# Sheet1.net
KiCad netlist of a schematic drawn in Altium Designer
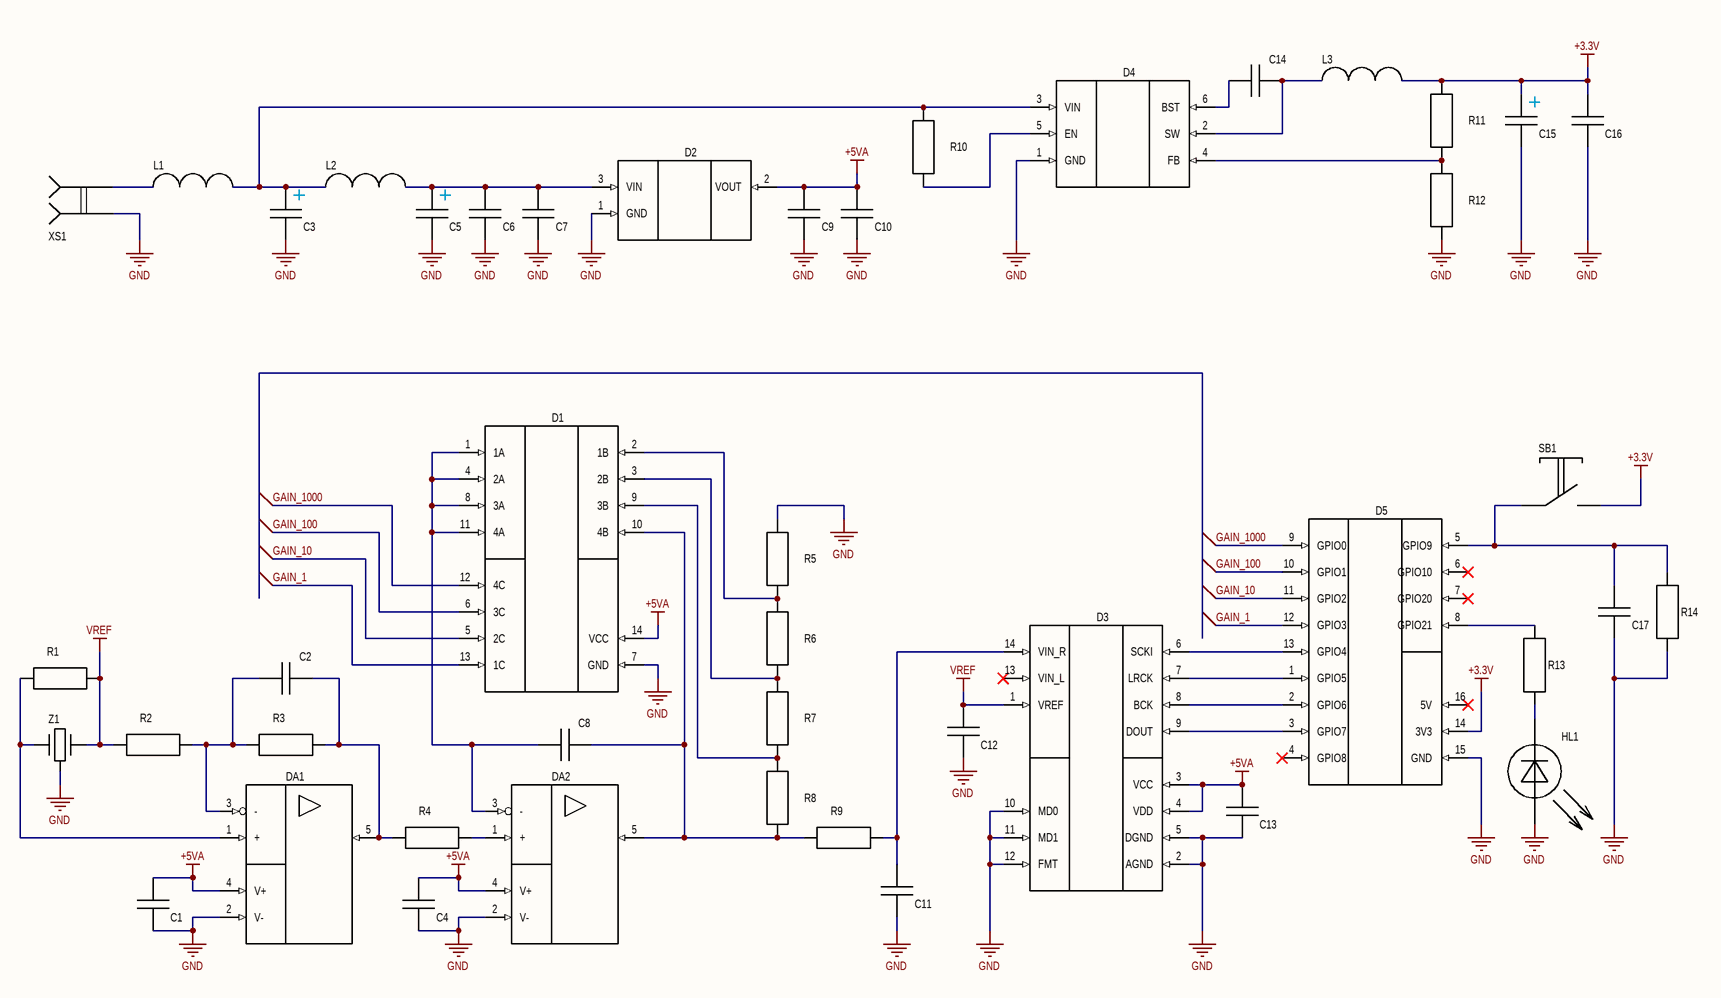
[diagram p0: Sheet1.SchDoc]

(export (version "E")
  (design (tool "Eeschema 10.0.6"))
  (components
    (comp (ref "C1")
      (value "100")
      (footprint "C_0603_(1608)")
      (description "Non-polarised capacitor")
      (fields (field (name "PART NUMBER") "GRM188R71H104KA93#") (field (name "MANUFACTURER") "MURATA"))
      (libsource (lib "GOSTBOM") (part "CAP_NONPOL"))
    )
    (comp (ref "C2")
      (value "100")
      (footprint "C_0603_(1608)")
      (description "Non-polarised capacitor")
      (fields (field (name "PART NUMBER") "GRM188R71H104KA93#") (field (name "MANUFACTURER") "MURATA"))
      (libsource (lib "GOSTBOM") (part "CAP_NONPOL"))
    )
    (comp (ref "C3")
      (value "100")
      (footprint "CP_D10_P5_L16")
      (description "Non-polarised capacitor")
      (fields (field (name "PART NUMBER") "GRM188R71H104KA93#") (field (name "MANUFACTURER") "MURATA"))
      (libsource (lib "GOSTBOM") (part "CAP_NONPOL"))
    )
    (comp (ref "C4")
      (value "100")
      (footprint "C_0603_(1608)")
      (description "Non-polarised capacitor")
      (fields (field (name "PART NUMBER") "GRM188R71H104KA93#") (field (name "MANUFACTURER") "MURATA"))
      (libsource (lib "GOSTBOM") (part "CAP_NONPOL"))
    )
    (comp (ref "C5")
      (value "100")
      (footprint "CP_D10_P5_L16")
      (description "Non-polarised capacitor")
      (fields (field (name "PART NUMBER") "GRM188R71H104KA93#") (field (name "MANUFACTURER") "MURATA"))
      (libsource (lib "GOSTBOM") (part "CAP_NONPOL"))
    )
    (comp (ref "C6")
      (value "100")
      (footprint "C_0603_(1608)")
      (description "Non-polarised capacitor")
      (fields (field (name "PART NUMBER") "GRM188R71H104KA93#") (field (name "MANUFACTURER") "MURATA"))
      (libsource (lib "GOSTBOM") (part "CAP_NONPOL"))
    )
    (comp (ref "C7")
      (value "100")
      (footprint "C_0603_(1608)")
      (description "Non-polarised capacitor")
      (fields (field (name "PART NUMBER") "GRM188R71H104KA93#") (field (name "MANUFACTURER") "MURATA"))
      (libsource (lib "GOSTBOM") (part "CAP_NONPOL"))
    )
    (comp (ref "C8")
      (value "100")
      (footprint "CAPC1608X90N")
      (description "Non-polarised capacitor")
      (fields (field (name "PART NUMBER") "GRM188R71H104KA93#") (field (name "MANUFACTURER") "MURATA"))
      (libsource (lib "GOSTBOM") (part "CAP_NONPOL"))
    )
    (comp (ref "C9")
      (value "100")
      (footprint "C_0603_(1608)")
      (description "Non-polarised capacitor")
      (fields (field (name "PART NUMBER") "GRM188R71H104KA93#") (field (name "MANUFACTURER") "MURATA"))
      (libsource (lib "GOSTBOM") (part "CAP_NONPOL"))
    )
    (comp (ref "C10")
      (value "100")
      (footprint "C_0603_(1608)")
      (description "Non-polarised capacitor")
      (fields (field (name "PART NUMBER") "GRM188R71H104KA93#") (field (name "MANUFACTURER") "MURATA"))
      (libsource (lib "GOSTBOM") (part "CAP_NONPOL"))
    )
    (comp (ref "C11")
      (value "100")
      (footprint "C_0603_(1608)")
      (description "Non-polarised capacitor")
      (fields (field (name "PART NUMBER") "GRM188R71H104KA93#") (field (name "MANUFACTURER") "MURATA"))
      (libsource (lib "GOSTBOM") (part "CAP_NONPOL"))
    )
    (comp (ref "C12")
      (value "100")
      (footprint "C_0603_(1608)")
      (description "Non-polarised capacitor")
      (fields (field (name "PART NUMBER") "GRM188R71H104KA93#") (field (name "MANUFACTURER") "MURATA"))
      (libsource (lib "GOSTBOM") (part "CAP_NONPOL"))
    )
    (comp (ref "C13")
      (value "100")
      (footprint "C_0603_(1608)")
      (description "Non-polarised capacitor")
      (fields (field (name "PART NUMBER") "GRM188R71H104KA93#") (field (name "MANUFACTURER") "MURATA"))
      (libsource (lib "GOSTBOM") (part "CAP_NONPOL"))
    )
    (comp (ref "C14")
      (value "100")
      (footprint "C_0603_(1608)")
      (description "Non-polarised capacitor")
      (fields (field (name "PART NUMBER") "GRM188R71H104KA93#") (field (name "MANUFACTURER") "MURATA"))
      (libsource (lib "GOSTBOM") (part "CAP_NONPOL"))
    )
    (comp (ref "C15")
      (value "100")
      (footprint "CP_D10_P5_L16")
      (description "Non-polarised capacitor")
      (fields (field (name "PART NUMBER") "GRM188R71H104KA93#") (field (name "MANUFACTURER") "MURATA"))
      (libsource (lib "GOSTBOM") (part "CAP_NONPOL"))
    )
    (comp (ref "C16")
      (value "100")
      (footprint "C_0603_(1608)")
      (description "Non-polarised capacitor")
      (fields (field (name "PART NUMBER") "GRM188R71H104KA93#") (field (name "MANUFACTURER") "MURATA"))
      (libsource (lib "GOSTBOM") (part "CAP_NONPOL"))
    )
    (comp (ref "C17")
      (value "100")
      (footprint "C_0603_(1608)")
      (description "Non-polarised capacitor")
      (fields (field (name "PART NUMBER") "GRM188R71H104KA93#") (field (name "MANUFACTURER") "MURATA"))
      (libsource (lib "GOSTBOM") (part "CAP_NONPOL"))
    )
    (comp (ref "D1")
      (value "Обозначение при заказе")
      (footprint "TSSOP14")
      (description "Описание свойств компонента")
      (libsource (lib "Schlib1") (part "SN74HC4066"))
    )
    (comp (ref "D2")
      (value "Обозначение при заказе")
      (footprint "SOT223")
      (description "Описание свойств компонента")
      (libsource (lib "Schlib1") (part "LD1117S50TR"))
    )
    (comp (ref "D3")
      (value "Обозначение при заказе")
      (footprint "SO-14")
      (description "Описание свойств компонента")
      (libsource (lib "Schlib1") (part "PCM1808"))
    )
    (comp (ref "D4")
      (value "Обозначение при заказе")
      (footprint "SOT23-6")
      (description "Описание свойств компонента")
      (libsource (lib "Schlib1") (part "MT1470"))
    )
    (comp (ref "D5")
      (value "Обозначение при заказе")
      (description "Описание свойств компонента")
      (libsource (lib "Schlib1") (part "ESP32C3"))
    )
    (comp (ref "DA1")
      (value "Обозначение при заказе")
      (footprint "TSOT23-5L")
      (description "Описание свойств компонента")
      (libsource (lib "Schlib1") (part "TLV6741"))
    )
    (comp (ref "DA2")
      (value "Обозначение при заказе")
      (footprint "TSOT23-5L")
      (description "Описание свойств компонента")
      (libsource (lib "Schlib1") (part "TLV6741"))
    )
    (comp (ref "HL1") (value "~") (footprint "ledrad3mm") (libsource (lib "sch") (part "LED")))
    (comp (ref "L1") (value "~") (footprint "C_0603_(1608)") (libsource (lib "sch") (part "Inductor")))
    (comp (ref "L2") (value "~") (footprint "C_0603_(1608)") (libsource (lib "sch") (part "Inductor")))
    (comp (ref "L3") (value "~") (footprint "SS0704") (libsource (lib "sch") (part "Inductor")))
    (comp (ref "R1")
      (value "CR 0402 4,7 кОм ±1%")
      (footprint "R_0603_(1608)")
      (fields (field (name "PART NUMBER") "CR0402-FX-4701G") (field (name "MANUFACTURER") "Bourns"))
      (libsource (lib "") (part "RESISTOR_1"))
    )
    (comp (ref "R2")
      (value "CR 0402 4,7 кОм ±1%")
      (footprint "R_0603_(1608)")
      (fields (field (name "PART NUMBER") "CR0402-FX-4701G") (field (name "MANUFACTURER") "Bourns"))
      (libsource (lib "") (part "RESISTOR_1"))
    )
    (comp (ref "R3")
      (value "CR 0402 4,7 кОм ±1%")
      (footprint "R_0603_(1608)")
      (fields (field (name "PART NUMBER") "CR0402-FX-4701G") (field (name "MANUFACTURER") "Bourns"))
      (libsource (lib "") (part "RESISTOR_1"))
    )
    (comp (ref "R4")
      (value "CR 0402 4,7 кОм ±1%")
      (footprint "R_0603_(1608)")
      (fields (field (name "PART NUMBER") "CR0402-FX-4701G") (field (name "MANUFACTURER") "Bourns"))
      (libsource (lib "") (part "RESISTOR_1"))
    )
    (comp (ref "R5")
      (value "CR 0402 4,7 кОм ±1%")
      (footprint "R_0603_(1608)")
      (fields (field (name "PART NUMBER") "CR0402-FX-4701G") (field (name "MANUFACTURER") "Bourns"))
      (libsource (lib "GOSTBOM") (part "RESISTOR"))
    )
    (comp (ref "R6")
      (value "CR 0402 4,7 кОм ±1%")
      (footprint "R_0603_(1608)")
      (fields (field (name "PART NUMBER") "CR0402-FX-4701G") (field (name "MANUFACTURER") "Bourns"))
      (libsource (lib "GOSTBOM") (part "RESISTOR"))
    )
    (comp (ref "R7")
      (value "CR 0402 4,7 кОм ±1%")
      (footprint "R_0603_(1608)")
      (fields (field (name "PART NUMBER") "CR0402-FX-4701G") (field (name "MANUFACTURER") "Bourns"))
      (libsource (lib "GOSTBOM") (part "RESISTOR"))
    )
    (comp (ref "R8")
      (value "CR 0402 4,7 кОм ±1%")
      (footprint "R_0603_(1608)")
      (fields (field (name "PART NUMBER") "CR0402-FX-4701G") (field (name "MANUFACTURER") "Bourns"))
      (libsource (lib "GOSTBOM") (part "RESISTOR"))
    )
    (comp (ref "R9")
      (value "CR 0402 4,7 кОм ±1%")
      (footprint "R_0603_(1608)")
      (fields (field (name "PART NUMBER") "CR0402-FX-4701G") (field (name "MANUFACTURER") "Bourns"))
      (libsource (lib "") (part "RESISTOR_1"))
    )
    (comp (ref "R10")
      (value "CR 0402 4,7 кОм ±1%")
      (footprint "R_0603_(1608)")
      (fields (field (name "PART NUMBER") "CR0402-FX-4701G") (field (name "MANUFACTURER") "Bourns"))
      (libsource (lib "GOSTBOM") (part "RESISTOR"))
    )
    (comp (ref "R11")
      (value "CR 0402 4,7 кОм ±1%")
      (footprint "R_0603_(1608)")
      (fields (field (name "PART NUMBER") "CR0402-FX-4701G") (field (name "MANUFACTURER") "Bourns"))
      (libsource (lib "GOSTBOM") (part "RESISTOR"))
    )
    (comp (ref "R12")
      (value "CR 0402 4,7 кОм ±1%")
      (footprint "R_0603_(1608)")
      (fields (field (name "PART NUMBER") "CR0402-FX-4701G") (field (name "MANUFACTURER") "Bourns"))
      (libsource (lib "GOSTBOM") (part "RESISTOR"))
    )
    (comp (ref "R13")
      (value "CR 0402 4,7 кОм ±1%")
      (footprint "R_0603_(1608)")
      (fields (field (name "PART NUMBER") "CR0402-FX-4701G") (field (name "MANUFACTURER") "Bourns"))
      (libsource (lib "GOSTBOM") (part "RESISTOR"))
    )
    (comp (ref "R14")
      (value "CR 0402 4,7 кОм ±1%")
      (footprint "R_0603_(1608)")
      (fields (field (name "PART NUMBER") "CR0402-FX-4701G") (field (name "MANUFACTURER") "Bourns"))
      (libsource (lib "GOSTBOM") (part "RESISTOR"))
    )
    (comp (ref "SB1") (value "~") (libsource (lib "sch") (part "SW-PB")))
    (comp (ref "XS1")
      (value "HYR-0142AR")
      (footprint "KLD-0202")
      (description "HYR-0142AR (GB-142AR) (BNC-7044), Разъем BNC, гнездо угловое, на плату")
      (libsource (lib "Connectors_templates") (part "XS2"))
    )
    (comp (ref "Z1") (value "~") (libsource (lib "sch") (part "XTALE")))
  )
  (nets
    (net (code "1") (name "+3.3V") (class "Default")
      (node (ref "C15") (pin "2") (pinfunction "2_2") (pintype "passive"))
      (node (ref "C16") (pin "2") (pinfunction "2_2") (pintype "passive"))
      (node (ref "D5") (pin "14") (pinfunction "3V3_14") (pintype "input"))
      (node (ref "L3") (pin "2") (pinfunction "2_2") (pintype "passive"))
      (node (ref "R11") (pin "2") (pinfunction "2_2") (pintype "passive"))
      (node (ref "SB1") (pin "2") (pinfunction "2_2") (pintype "passive"))
    )
    (net (code "2") (name "+5VA") (class "Default")
      (node (ref "C1") (pin "2") (pinfunction "2_2") (pintype "passive"))
      (node (ref "C10") (pin "2") (pinfunction "2_2") (pintype "passive"))
      (node (ref "C13") (pin "2") (pinfunction "2_2") (pintype "passive"))
      (node (ref "C4") (pin "2") (pinfunction "2_2") (pintype "passive"))
      (node (ref "C9") (pin "2") (pinfunction "2_2") (pintype "passive"))
      (node (ref "D1") (pin "14") (pinfunction "VCC_14") (pintype "input"))
      (node (ref "D2") (pin "2") (pinfunction "VOUT_2") (pintype "input"))
      (node (ref "D3") (pin "3") (pinfunction "VCC_3") (pintype "input"))
      (node (ref "D3") (pin "4") (pinfunction "VDD_4") (pintype "input"))
      (node (ref "DA1") (pin "4") (pinfunction "V+_4") (pintype "input"))
      (node (ref "DA2") (pin "4") (pinfunction "V+_4") (pintype "input"))
    )
    (net (code "3") (name "/GAIN_1") (class "Default")
      (node (ref "D1") (pin "13") (pinfunction "1C_13") (pintype "input"))
      (node (ref "D5") (pin "12") (pinfunction "GPIO3_12") (pintype "input"))
    )
    (net (code "4") (name "/GAIN_10") (class "Default")
      (node (ref "D1") (pin "5") (pinfunction "2C_5") (pintype "input"))
      (node (ref "D5") (pin "11") (pinfunction "GPIO2_11") (pintype "input"))
    )
    (net (code "5") (name "/GAIN_100") (class "Default")
      (node (ref "D1") (pin "6") (pinfunction "3C_6") (pintype "input"))
      (node (ref "D5") (pin "10") (pinfunction "GPIO1_10") (pintype "input"))
    )
    (net (code "6") (name "/GAIN_1000") (class "Default")
      (node (ref "D1") (pin "12") (pinfunction "4C_12") (pintype "input"))
      (node (ref "D5") (pin "9") (pinfunction "GPIO0_9") (pintype "input"))
    )
    (net (code "7") (name "GND") (class "Default")
      (node (ref "C1") (pin "1") (pinfunction "1_1") (pintype "passive"))
      (node (ref "C10") (pin "1") (pinfunction "1_1") (pintype "passive"))
      (node (ref "C11") (pin "1") (pinfunction "1_1") (pintype "passive"))
      (node (ref "C12") (pin "1") (pinfunction "1_1") (pintype "passive"))
      (node (ref "C13") (pin "1") (pinfunction "1_1") (pintype "passive"))
      (node (ref "C15") (pin "1") (pinfunction "1_1") (pintype "passive"))
      (node (ref "C16") (pin "1") (pinfunction "1_1") (pintype "passive"))
      (node (ref "C17") (pin "1") (pinfunction "1_1") (pintype "passive"))
      (node (ref "C3") (pin "1") (pinfunction "1_1") (pintype "passive"))
      (node (ref "C4") (pin "1") (pinfunction "1_1") (pintype "passive"))
      (node (ref "C5") (pin "1") (pinfunction "1_1") (pintype "passive"))
      (node (ref "C6") (pin "1") (pinfunction "1_1") (pintype "passive"))
      (node (ref "C7") (pin "1") (pinfunction "1_1") (pintype "passive"))
      (node (ref "C9") (pin "1") (pinfunction "1_1") (pintype "passive"))
      (node (ref "D1") (pin "7") (pinfunction "GND_7") (pintype "input"))
      (node (ref "D2") (pin "1") (pinfunction "GND_1") (pintype "input"))
      (node (ref "D3") (pin "10") (pinfunction "MD0_10") (pintype "input"))
      (node (ref "D3") (pin "11") (pinfunction "MD1_11") (pintype "input"))
      (node (ref "D3") (pin "12") (pinfunction "FMT_12") (pintype "input"))
      (node (ref "D3") (pin "2") (pinfunction "AGND_2") (pintype "input"))
      (node (ref "D3") (pin "5") (pinfunction "DGND_5") (pintype "input"))
      (node (ref "D4") (pin "1") (pinfunction "GND_1") (pintype "input"))
      (node (ref "D5") (pin "15") (pinfunction "GND_15") (pintype "input"))
      (node (ref "DA1") (pin "2") (pinfunction "V-_2") (pintype "input"))
      (node (ref "DA2") (pin "2") (pinfunction "V-_2") (pintype "input"))
      (node (ref "HL1") (pin "1") (pinfunction "A_1") (pintype "passive"))
      (node (ref "R12") (pin "1") (pinfunction "1_1") (pintype "passive"))
      (node (ref "R14") (pin "1") (pinfunction "1_1") (pintype "passive"))
      (node (ref "R5") (pin "2") (pinfunction "2_2") (pintype "passive"))
      (node (ref "XS1") (pin "1") (pinfunction "1_1") (pintype "passive"))
      (node (ref "Z1") (pin "E") (pinfunction "E_E") (pintype "passive"))
    )
    (net (code "8") (name "Net-(C2-Pad2)") (class "Default")
      (node (ref "C2") (pin "2") (pinfunction "2_2") (pintype "passive"))
      (node (ref "DA1") (pin "5") (pintype "input"))
      (node (ref "R3") (pin "2") (pinfunction "2_2") (pintype "passive"))
      (node (ref "R4") (pin "1") (pinfunction "1_1") (pintype "passive"))
    )
    (net (code "9") (name "Net-(D1-1A)") (class "Default")
      (node (ref "C8") (pin "1") (pinfunction "1_1") (pintype "passive"))
      (node (ref "D1") (pin "1") (pinfunction "1A_1") (pintype "input"))
      (node (ref "D1") (pin "11") (pinfunction "4A_11") (pintype "input"))
      (node (ref "D1") (pin "4") (pinfunction "2A_4") (pintype "input"))
      (node (ref "D1") (pin "8") (pinfunction "3A_8") (pintype "input"))
      (node (ref "DA2") (pin "3") (pinfunction "-_3") (pintype "input"))
    )
    (net (code "10") (name "Net-(D1-1B)") (class "Default")
      (node (ref "D1") (pin "2") (pinfunction "1B_2") (pintype "input"))
      (node (ref "R5") (pin "1") (pinfunction "1_1") (pintype "passive"))
      (node (ref "R6") (pin "2") (pinfunction "2_2") (pintype "passive"))
    )
    (net (code "11") (name "Net-(D1-2B)") (class "Default")
      (node (ref "D1") (pin "3") (pinfunction "2B_3") (pintype "input"))
      (node (ref "R6") (pin "1") (pinfunction "1_1") (pintype "passive"))
      (node (ref "R7") (pin "2") (pinfunction "2_2") (pintype "passive"))
    )
    (net (code "12") (name "Net-(D1-3B)") (class "Default")
      (node (ref "D1") (pin "9") (pinfunction "3B_9") (pintype "input"))
      (node (ref "R7") (pin "1") (pinfunction "1_1") (pintype "passive"))
      (node (ref "R8") (pin "2") (pinfunction "2_2") (pintype "passive"))
    )
    (net (code "13") (name "Net-(D1-4B)") (class "Default")
      (node (ref "C8") (pin "2") (pinfunction "2_2") (pintype "passive"))
      (node (ref "D1") (pin "10") (pinfunction "4B_10") (pintype "input"))
      (node (ref "DA2") (pin "5") (pintype "input"))
      (node (ref "R8") (pin "1") (pinfunction "1_1") (pintype "passive"))
      (node (ref "R9") (pin "1") (pinfunction "1_1") (pintype "passive"))
    )
    (net (code "14") (name "Net-(D2-VIN)") (class "Default")
      (node (ref "C5") (pin "2") (pinfunction "2_2") (pintype "passive"))
      (node (ref "C6") (pin "2") (pinfunction "2_2") (pintype "passive"))
      (node (ref "C7") (pin "2") (pinfunction "2_2") (pintype "passive"))
      (node (ref "D2") (pin "3") (pinfunction "VIN_3") (pintype "input"))
      (node (ref "L2") (pin "2") (pinfunction "2_2") (pintype "passive"))
    )
    (net (code "15") (name "Net-(D3-BCK)") (class "Default")
      (node (ref "D3") (pin "8") (pinfunction "BCK_8") (pintype "input"))
      (node (ref "D5") (pin "2") (pinfunction "GPIO6_2") (pintype "input"))
    )
    (net (code "16") (name "Net-(D3-DOUT)") (class "Default")
      (node (ref "D3") (pin "9") (pinfunction "DOUT_9") (pintype "input"))
      (node (ref "D5") (pin "3") (pinfunction "GPIO7_3") (pintype "input"))
    )
    (net (code "17") (name "Net-(D3-LRCK)") (class "Default")
      (node (ref "D3") (pin "7") (pinfunction "LRCK_7") (pintype "input"))
      (node (ref "D5") (pin "1") (pinfunction "GPIO5_1") (pintype "input"))
    )
    (net (code "18") (name "Net-(D3-SCKI)") (class "Default")
      (node (ref "D3") (pin "6") (pinfunction "SCKI_6") (pintype "input"))
      (node (ref "D5") (pin "13") (pinfunction "GPIO4_13") (pintype "input"))
    )
    (net (code "19") (name "Net-(D3-VIN_R)") (class "Default")
      (node (ref "C11") (pin "2") (pinfunction "2_2") (pintype "passive"))
      (node (ref "D3") (pin "14") (pinfunction "VIN_R_14") (pintype "input"))
      (node (ref "R9") (pin "2") (pinfunction "2_2") (pintype "passive"))
    )
    (net (code "20") (name "Net-(D4-BST)") (class "Default")
      (node (ref "C14") (pin "1") (pinfunction "1_1") (pintype "passive"))
      (node (ref "D4") (pin "6") (pinfunction "BST_6") (pintype "input"))
    )
    (net (code "21") (name "Net-(D4-EN)") (class "Default")
      (node (ref "D4") (pin "5") (pinfunction "EN_5") (pintype "input"))
      (node (ref "R10") (pin "1") (pinfunction "1_1") (pintype "passive"))
    )
    (net (code "22") (name "Net-(D4-FB)") (class "Default")
      (node (ref "D4") (pin "4") (pinfunction "FB_4") (pintype "input"))
      (node (ref "R11") (pin "1") (pinfunction "1_1") (pintype "passive"))
      (node (ref "R12") (pin "2") (pinfunction "2_2") (pintype "passive"))
    )
    (net (code "23") (name "Net-(D4-SW)") (class "Default")
      (node (ref "C14") (pin "2") (pinfunction "2_2") (pintype "passive"))
      (node (ref "D4") (pin "2") (pinfunction "SW_2") (pintype "input"))
      (node (ref "L3") (pin "1") (pinfunction "1_1") (pintype "passive"))
    )
    (net (code "24") (name "Net-(D4-VIN)") (class "Default")
      (node (ref "C3") (pin "2") (pinfunction "2_2") (pintype "passive"))
      (node (ref "D4") (pin "3") (pinfunction "VIN_3") (pintype "input"))
      (node (ref "L1") (pin "2") (pinfunction "2_2") (pintype "passive"))
      (node (ref "L2") (pin "1") (pinfunction "1_1") (pintype "passive"))
      (node (ref "R10") (pin "2") (pinfunction "2_2") (pintype "passive"))
    )
    (net (code "25") (name "Net-(D5-GPIO9)") (class "Default")
      (node (ref "C17") (pin "2") (pinfunction "2_2") (pintype "passive"))
      (node (ref "D5") (pin "5") (pinfunction "GPIO9_5") (pintype "input"))
      (node (ref "R14") (pin "2") (pinfunction "2_2") (pintype "passive"))
      (node (ref "SB1") (pin "1") (pinfunction "1_1") (pintype "passive"))
    )
    (net (code "26") (name "Net-(D5-GPIO21)") (class "Default")
      (node (ref "D5") (pin "8") (pinfunction "GPIO21_8") (pintype "input"))
      (node (ref "R13") (pin "2") (pinfunction "2_2") (pintype "passive"))
    )
    (net (code "27") (name "Net-(DA1-+)") (class "Default")
      (node (ref "DA1") (pin "1") (pinfunction "+_1") (pintype "input"))
      (node (ref "R1") (pin "1") (pinfunction "1_1") (pintype "passive"))
      (node (ref "Z1") (pin "1") (pinfunction "OSC1_1") (pintype "passive"))
    )
    (net (code "28") (name "Net-(DA1--)") (class "Default")
      (node (ref "C2") (pin "1") (pinfunction "1_1") (pintype "passive"))
      (node (ref "DA1") (pin "3") (pinfunction "-_3") (pintype "input"))
      (node (ref "R2") (pin "2") (pinfunction "2_2") (pintype "passive"))
      (node (ref "R3") (pin "1") (pinfunction "1_1") (pintype "passive"))
    )
    (net (code "29") (name "Net-(DA2-+)") (class "Default")
      (node (ref "DA2") (pin "1") (pinfunction "+_1") (pintype "input"))
      (node (ref "R4") (pin "2") (pinfunction "2_2") (pintype "passive"))
    )
    (net (code "30") (name "Net-(HL1-C)") (class "Default")
      (node (ref "HL1") (pin "2") (pinfunction "C_2") (pintype "passive"))
      (node (ref "R13") (pin "1") (pinfunction "1_1") (pintype "passive"))
    )
    (net (code "31") (name "Net-(L1-Pad1)") (class "Default")
      (node (ref "L1") (pin "1") (pinfunction "1_1") (pintype "passive"))
      (node (ref "XS1") (pin "2") (pinfunction "2_2") (pintype "passive"))
    )
    (net (code "32") (name "VREF") (class "Default")
      (node (ref "C12") (pin "2") (pinfunction "2_2") (pintype "passive"))
      (node (ref "D3") (pin "1") (pinfunction "VREF_1") (pintype "input"))
      (node (ref "R1") (pin "2") (pinfunction "2_2") (pintype "passive"))
      (node (ref "R2") (pin "1") (pinfunction "1_1") (pintype "passive"))
      (node (ref "Z1") (pin "3") (pinfunction "OSC2_3") (pintype "passive"))
    )
    (net (code "33") (name "unconnected-(D3-VIN_L-Pad13)") (class "Default")
      (node (ref "D3") (pin "13") (pinfunction "VIN_L_13") (pintype "input+no_connect"))
    )
    (net (code "34") (name "unconnected-(D5-5V-Pad16)") (class "Default")
      (node (ref "D5") (pin "16") (pinfunction "5V_16") (pintype "input+no_connect"))
    )
    (net (code "35") (name "unconnected-(D5-GPIO8-Pad4)") (class "Default")
      (node (ref "D5") (pin "4") (pinfunction "GPIO8_4") (pintype "input+no_connect"))
    )
    (net (code "36") (name "unconnected-(D5-GPIO10-Pad6)") (class "Default")
      (node (ref "D5") (pin "6") (pinfunction "GPIO10_6") (pintype "input+no_connect"))
    )
    (net (code "37") (name "unconnected-(D5-GPIO20-Pad7)") (class "Default")
      (node (ref "D5") (pin "7") (pinfunction "GPIO20_7") (pintype "input+no_connect"))
    )
  )
)
